# mcu.net
KiCad netlist of a schematic drawn in Altium Designer
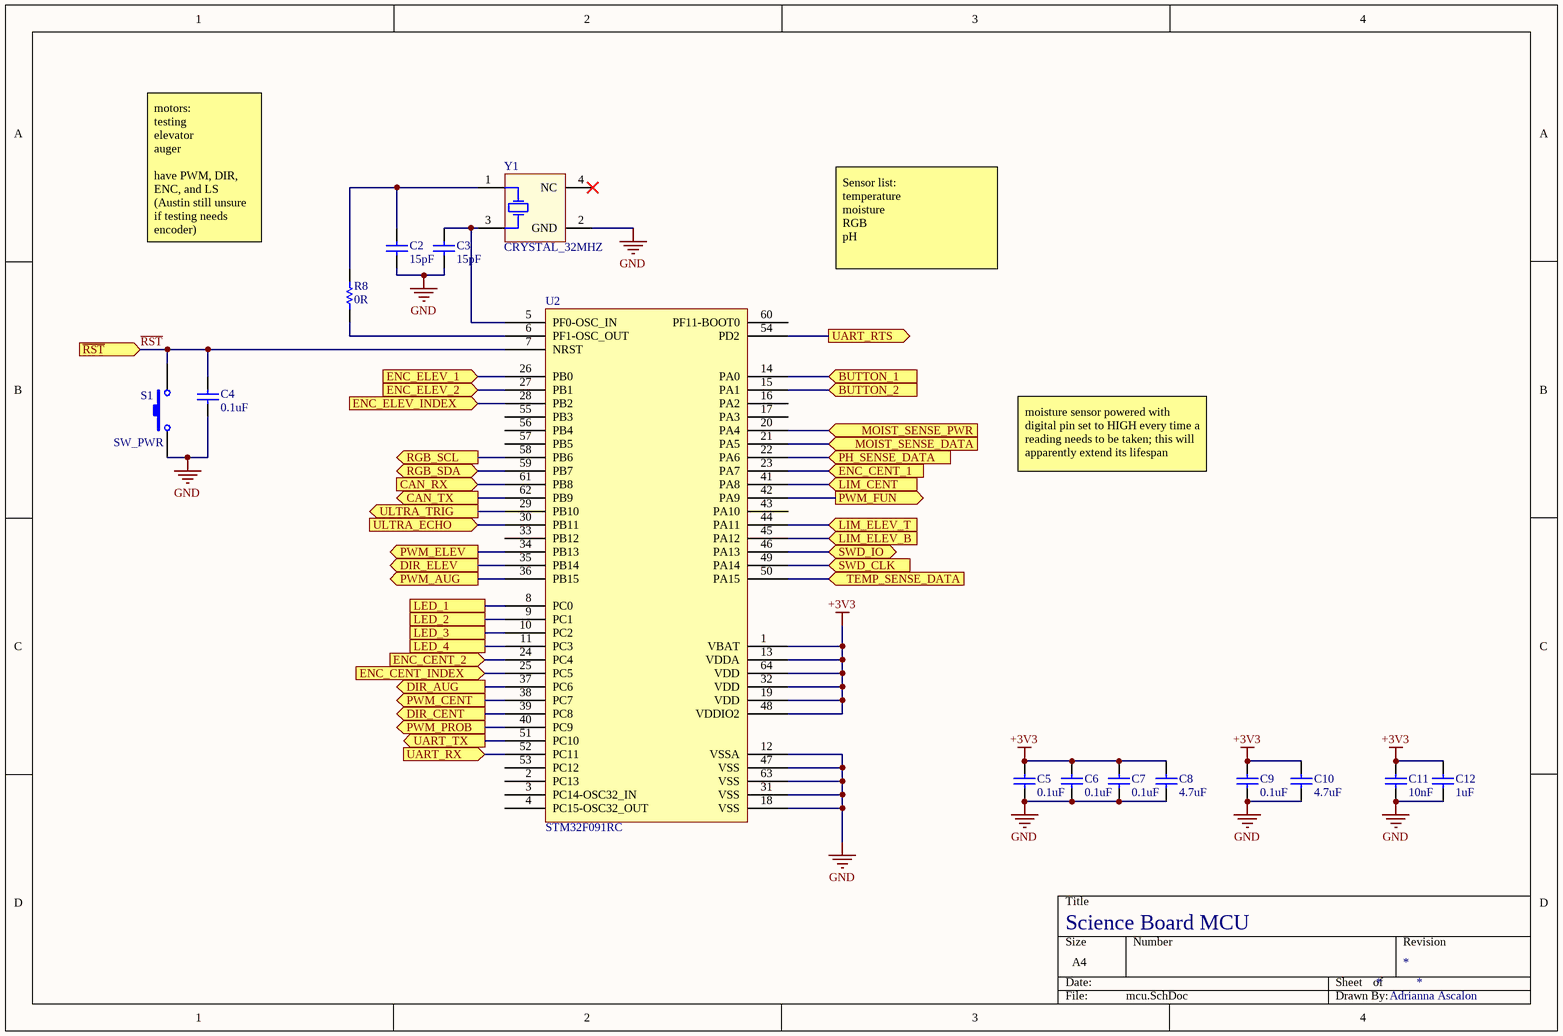
[diagram p0: mcu.SchDoc]

(export (version "E")
  (design (tool "Eeschema 10.0.6"))
  (components
    (comp (ref "C2")
      (value "15pF")
      (footprint "CAPC0603(1608)55_N")
      (description "CAP CER 15PF 250V NPO 0603")
      (fields (field (name "MANUFACTURER") "Yageo") (field (name "MPN") "AC0603JRNPOYBN150"))
      (libsource (lib "UWRT_Schematic_Library_2019") (part "CAP_15pF_0603"))
    )
    (comp (ref "C3")
      (value "15pF")
      (footprint "CAPC0603(1608)55_N")
      (description "CAP CER 15PF 250V NPO 0603")
      (fields (field (name "MANUFACTURER") "Yageo") (field (name "MPN") "AC0603JRNPOYBN150"))
      (libsource (lib "UWRT_Schematic_Library_2019") (part "CAP_15pF_0603"))
    )
    (comp (ref "C4")
      (value "0.1uF")
      (footprint "CAPC0603(1608)55_N")
      (description "CAP CER 0.1UF 16V X7R 0603")
      (fields (field (name "MANUFACTURER") "Yageo") (field (name "MPN") "CC0603KRX7R7BB104"))
      (libsource (lib "UWRT_Schematic_Library_2019") (part "CAP_0.1uF_16V_0603"))
    )
    (comp (ref "C5")
      (value "0.1uF")
      (footprint "CAPC0603(1608)55_N")
      (description "CAP CER 0.1UF 16V X7R 0603")
      (fields (field (name "MANUFACTURER") "Yageo") (field (name "MPN") "CC0603KRX7R7BB104"))
      (libsource (lib "UWRT_Schematic_Library_2019") (part "CAP_0.1uF_16V_0603"))
    )
    (comp (ref "C6")
      (value "0.1uF")
      (footprint "CAPC0603(1608)55_N")
      (description "CAP CER 0.1UF 16V X7R 0603")
      (fields (field (name "MANUFACTURER") "Yageo") (field (name "MPN") "CC0603KRX7R7BB104"))
      (libsource (lib "UWRT_Schematic_Library_2019") (part "CAP_0.1uF_16V_0603"))
    )
    (comp (ref "C7")
      (value "0.1uF")
      (footprint "CAPC0603(1608)55_N")
      (description "CAP CER 0.1UF 16V X7R 0603")
      (fields (field (name "MANUFACTURER") "Yageo") (field (name "MPN") "CC0603KRX7R7BB104"))
      (libsource (lib "UWRT_Schematic_Library_2019") (part "CAP_0.1uF_16V_0603"))
    )
    (comp (ref "C8")
      (value "4.7uF")
      (footprint "CAPC0603(1608)55_N")
      (description "CAP CER 4.7UF 6.3V X5R 0603")
      (fields (field (name "MANUFACTURER") "Yageo") (field (name "MPN") "CC0603KRX5R5BB475"))
      (libsource (lib "UWRT_Schematic_Library_2019") (part "CAP_4.7uF_0603"))
    )
    (comp (ref "C9")
      (value "0.1uF")
      (footprint "CAPC0603(1608)55_N")
      (description "CAP CER 0.1UF 16V X7R 0603")
      (fields (field (name "MANUFACTURER") "Yageo") (field (name "MPN") "CC0603KRX7R7BB104"))
      (libsource (lib "UWRT_Schematic_Library_2019") (part "CAP_0.1uF_16V_0603"))
    )
    (comp (ref "C10")
      (value "4.7uF")
      (footprint "CAPC0603(1608)55_N")
      (description "CAP CER 4.7UF 6.3V X5R 0603")
      (fields (field (name "MANUFACTURER") "Yageo") (field (name "MPN") "CC0603KRX5R5BB475"))
      (libsource (lib "UWRT_Schematic_Library_2019") (part "CAP_4.7uF_0603"))
    )
    (comp (ref "C11")
      (value "10nF")
      (footprint "CAPC0603(1608)55_N")
      (description "CAP CER 10000PF 16V X7R 0603")
      (fields (field (name "MANUFACTURER") "Yageo") (field (name "MPN") "CC0603KRX7R7BB103"))
      (libsource (lib "UWRT_Schematic_Library_2019") (part "CAP_10nF_0603"))
    )
    (comp (ref "C12")
      (value "1uF")
      (footprint "CAPC0603(1608)55_N")
      (description "CAP CER 1UF 16V Y5V 0603")
      (fields (field (name "MANUFACTURER") "Yageo") (field (name "MPN") "CC0603ZRY5V7BB105"))
      (libsource (lib "UWRT_Schematic_Library_2019") (part "CAP_1uF_16V_0603"))
    )
    (comp (ref "R8")
      (value "0R")
      (footprint "RESC0603(1608)_N")
      (description "RES SMD 0 OHM JUMPER 1/10W 0603")
      (fields (field (name "MANUFACTURER") "Yageo") (field (name "MPN") "RC0603JR-070RL"))
      (libsource (lib "UWRT_Schematic_Library_2019") (part "RES_0R_0603"))
    )
    (comp (ref "S1")
      (value "SW_PWR")
      (footprint "PTS830GM140")
      (description "Power Switch (Red)")
      (fields
        (field (name "MPN") "PTS830GM140 SMTR LFS")
        (field (name "DIGIKEY PART NUMBER") "CKN10587CT-ND")
      )
      (libsource (lib "UWRT_Schematic_Library_2019") (part "SW_PWR"))
    )
    (comp (ref "U2")
      (value "STM32F091RC")
      (footprint "UWRT_Footprint_Library_2019:STM_LQFP64_N")
      (fields
        (field (name "MANUFACTURER") "STMicroelectronics")
        (field (name "DIGIKEY PART NUMBER") "497-15167-ND")
      )
      (libsource (lib "UWRT_Schematic_Library_2019") (part "STM32F091RC"))
    )
    (comp (ref "Y1")
      (value "CRYSTAL_32MHZ")
      (footprint "AVX-CX2520DB32000D0GEJZ1-4_V")
      (description "CRYSTAL 32MHZ 8PF SMD")
      (fields
        (field (name "MANUFACTURER") "Kyocera International Inc. Electronic Components")
        (field (name "MPN") "CX2520DB32000D0GPSC1")
      )
      (libsource (lib "UWRT_Schematic_Library_2019") (part "CRYSTAL_32MHZ"))
    )
  )
  (nets
    (net (code "1") (name "+3V3") (class "Default")
      (node (ref "C10") (pin "2") (pinfunction "2_2") (pintype "passive"))
      (node (ref "C11") (pin "2") (pinfunction "2_2") (pintype "passive"))
      (node (ref "C12") (pin "2") (pinfunction "2_2") (pintype "passive"))
      (node (ref "C5") (pin "1") (pinfunction "1_1") (pintype "passive"))
      (node (ref "C6") (pin "1") (pinfunction "1_1") (pintype "passive"))
      (node (ref "C7") (pin "1") (pinfunction "1_1") (pintype "passive"))
      (node (ref "C8") (pin "2") (pinfunction "2_2") (pintype "passive"))
      (node (ref "C9") (pin "1") (pinfunction "1_1") (pintype "passive"))
      (node (ref "U2") (pin "1") (pinfunction "VBAT_1") (pintype "passive"))
      (node (ref "U2") (pin "13") (pinfunction "VDDA_13") (pintype "passive"))
      (node (ref "U2") (pin "19") (pinfunction "VDD_19") (pintype "passive"))
      (node (ref "U2") (pin "32") (pinfunction "VDD_32") (pintype "passive"))
      (node (ref "U2") (pin "48") (pinfunction "VDDIO2_48") (pintype "passive"))
      (node (ref "U2") (pin "64") (pinfunction "VDD_64") (pintype "passive"))
    )
    (net (code "2") (name "/BUTTON_1") (class "Default")
      (node (ref "U2") (pin "14") (pinfunction "PA0_14") (pintype "passive"))
    )
    (net (code "3") (name "/BUTTON_2") (class "Default")
      (node (ref "U2") (pin "15") (pinfunction "PA1_15") (pintype "passive"))
    )
    (net (code "4") (name "/CAN_RX") (class "Default")
      (node (ref "U2") (pin "61") (pinfunction "PB8_61") (pintype "passive"))
    )
    (net (code "5") (name "/CAN_TX") (class "Default")
      (node (ref "U2") (pin "62") (pinfunction "PB9_62") (pintype "passive"))
    )
    (net (code "6") (name "/DIR_AUG") (class "Default")
      (node (ref "U2") (pin "37") (pinfunction "PC6_37") (pintype "passive"))
    )
    (net (code "7") (name "/DIR_CENT") (class "Default")
      (node (ref "U2") (pin "39") (pinfunction "PC8_39") (pintype "passive"))
    )
    (net (code "8") (name "/DIR_ELEV") (class "Default")
      (node (ref "U2") (pin "35") (pinfunction "PB14_35") (pintype "passive"))
    )
    (net (code "9") (name "/ENC_CENT_1") (class "Default")
      (node (ref "U2") (pin "23") (pinfunction "PA7_23") (pintype "passive"))
    )
    (net (code "10") (name "/ENC_CENT_2") (class "Default")
      (node (ref "U2") (pin "24") (pinfunction "PC4_24") (pintype "passive"))
    )
    (net (code "11") (name "/ENC_CENT_INDEX") (class "Default")
      (node (ref "U2") (pin "25") (pinfunction "PC5_25") (pintype "passive"))
    )
    (net (code "12") (name "/ENC_ELEV_1") (class "Default")
      (node (ref "U2") (pin "26") (pinfunction "PB0_26") (pintype "passive"))
    )
    (net (code "13") (name "/ENC_ELEV_2") (class "Default")
      (node (ref "U2") (pin "27") (pinfunction "PB1_27") (pintype "passive"))
    )
    (net (code "14") (name "/ENC_ELEV_INDEX") (class "Default")
      (node (ref "U2") (pin "28") (pinfunction "PB2_28") (pintype "passive"))
    )
    (net (code "15") (name "/LED_1") (class "Default")
      (node (ref "U2") (pin "8") (pinfunction "PC0_8") (pintype "passive"))
    )
    (net (code "16") (name "/LED_2") (class "Default")
      (node (ref "U2") (pin "9") (pinfunction "PC1_9") (pintype "passive"))
    )
    (net (code "17") (name "/LED_3") (class "Default")
      (node (ref "U2") (pin "10") (pinfunction "PC2_10") (pintype "passive"))
    )
    (net (code "18") (name "/LED_4") (class "Default")
      (node (ref "U2") (pin "11") (pinfunction "PC3_11") (pintype "passive"))
    )
    (net (code "19") (name "/LIM_CENT") (class "Default")
      (node (ref "U2") (pin "41") (pinfunction "PA8_41") (pintype "passive"))
    )
    (net (code "20") (name "/LIM_ELEV_B") (class "Default")
      (node (ref "U2") (pin "45") (pinfunction "PA12_45") (pintype "passive"))
    )
    (net (code "21") (name "/LIM_ELEV_T") (class "Default")
      (node (ref "U2") (pin "44") (pinfunction "PA11_44") (pintype "passive"))
    )
    (net (code "22") (name "/MOIST_SENSE_DATA") (class "Default")
      (node (ref "U2") (pin "21") (pinfunction "PA5_21") (pintype "passive"))
    )
    (net (code "23") (name "/MOIST_SENSE_PWR") (class "Default")
      (node (ref "U2") (pin "20") (pinfunction "PA4_20") (pintype "passive"))
    )
    (net (code "24") (name "/PH_SENSE_DATA") (class "Default")
      (node (ref "U2") (pin "22") (pinfunction "PA6_22") (pintype "passive"))
    )
    (net (code "25") (name "/PWM_AUG") (class "Default")
      (node (ref "U2") (pin "36") (pinfunction "PB15_36") (pintype "passive"))
    )
    (net (code "26") (name "/PWM_CENT") (class "Default")
      (node (ref "U2") (pin "38") (pinfunction "PC7_38") (pintype "passive"))
    )
    (net (code "27") (name "/PWM_ELEV") (class "Default")
      (node (ref "U2") (pin "34") (pinfunction "PB13_34") (pintype "passive"))
    )
    (net (code "28") (name "/PWM_FUN") (class "Default")
      (node (ref "U2") (pin "42") (pinfunction "PA9_42") (pintype "passive"))
    )
    (net (code "29") (name "/PWM_PROB") (class "Default")
      (node (ref "U2") (pin "40") (pinfunction "PC9_40") (pintype "passive"))
    )
    (net (code "30") (name "/RGB_SCL") (class "Default")
      (node (ref "U2") (pin "58") (pinfunction "PB6_58") (pintype "passive"))
    )
    (net (code "31") (name "/RGB_SDA") (class "Default")
      (node (ref "U2") (pin "59") (pinfunction "PB7_59") (pintype "passive"))
    )
    (net (code "32") (name "/SWD_CLK") (class "Default")
      (node (ref "U2") (pin "49") (pinfunction "PA14_49") (pintype "passive"))
    )
    (net (code "33") (name "/SWD_IO") (class "Default")
      (node (ref "U2") (pin "46") (pinfunction "PA13_46") (pintype "passive"))
    )
    (net (code "34") (name "/TEMP_SENSE_DATA") (class "Default")
      (node (ref "U2") (pin "50") (pinfunction "PA15_50") (pintype "passive"))
    )
    (net (code "35") (name "/UART_RTS") (class "Default")
      (node (ref "U2") (pin "54") (pinfunction "PD2_54") (pintype "passive"))
    )
    (net (code "36") (name "/UART_RX") (class "Default")
      (node (ref "U2") (pin "52") (pinfunction "PC11_52") (pintype "passive"))
    )
    (net (code "37") (name "/UART_TX") (class "Default")
      (node (ref "U2") (pin "51") (pinfunction "PC10_51") (pintype "passive"))
    )
    (net (code "38") (name "/ULTRA_ECHO") (class "Default")
      (node (ref "U2") (pin "30") (pinfunction "PB11_30") (pintype "passive"))
    )
    (net (code "39") (name "/ULTRA_TRIG") (class "Default")
      (node (ref "U2") (pin "29") (pinfunction "PB10_29") (pintype "passive"))
    )
    (net (code "40") (name "/~{RST}") (class "Default")
      (node (ref "C4") (pin "2") (pinfunction "2_2") (pintype "passive"))
      (node (ref "S1") (pin "2") (pinfunction "2_2") (pintype "passive"))
      (node (ref "U2") (pin "7") (pinfunction "NRST_7") (pintype "passive"))
    )
    (net (code "41") (name "GND") (class "Default")
      (node (ref "C10") (pin "1") (pinfunction "1_1") (pintype "passive"))
      (node (ref "C11") (pin "1") (pinfunction "1_1") (pintype "passive"))
      (node (ref "C12") (pin "1") (pinfunction "1_1") (pintype "passive"))
      (node (ref "C2") (pin "1") (pinfunction "1_1") (pintype "passive"))
      (node (ref "C3") (pin "1") (pinfunction "1_1") (pintype "passive"))
      (node (ref "C4") (pin "1") (pinfunction "1_1") (pintype "passive"))
      (node (ref "C5") (pin "2") (pinfunction "2_2") (pintype "passive"))
      (node (ref "C6") (pin "2") (pinfunction "2_2") (pintype "passive"))
      (node (ref "C7") (pin "2") (pinfunction "2_2") (pintype "passive"))
      (node (ref "C8") (pin "1") (pinfunction "1_1") (pintype "passive"))
      (node (ref "C9") (pin "2") (pinfunction "2_2") (pintype "passive"))
      (node (ref "S1") (pin "1") (pinfunction "1_1") (pintype "passive"))
      (node (ref "U2") (pin "12") (pinfunction "VSSA_12") (pintype "passive"))
      (node (ref "U2") (pin "18") (pinfunction "VSS_18") (pintype "passive"))
      (node (ref "U2") (pin "31") (pinfunction "VSS_31") (pintype "passive"))
      (node (ref "U2") (pin "47") (pinfunction "VSS_47") (pintype "passive"))
      (node (ref "U2") (pin "63") (pinfunction "VSS_63") (pintype "passive"))
      (node (ref "Y1") (pin "2") (pinfunction "GND_2") (pintype "power_in"))
    )
    (net (code "42") (name "Net-(C2-Pad2)") (class "Default")
      (node (ref "C2") (pin "2") (pinfunction "2_2") (pintype "passive"))
      (node (ref "R8") (pin "2") (pinfunction "2_2") (pintype "passive"))
      (node (ref "Y1") (pin "1") (pinfunction "HOT_1") (pintype "passive"))
    )
    (net (code "43") (name "Net-(U2-PF0-OSC_IN)") (class "Default")
      (node (ref "C3") (pin "2") (pinfunction "2_2") (pintype "passive"))
      (node (ref "U2") (pin "5") (pinfunction "PF0-OSC_IN_5") (pintype "passive"))
      (node (ref "Y1") (pin "3") (pinfunction "HOT_3") (pintype "passive"))
    )
    (net (code "44") (name "Net-(U2-PF1-OSC_OUT)") (class "Default")
      (node (ref "R8") (pin "1") (pinfunction "1_1") (pintype "passive"))
      (node (ref "U2") (pin "6") (pinfunction "PF1-OSC_OUT_6") (pintype "passive"))
    )
    (net (code "45") (name "unconnected-(U2-PA2-Pad16)") (class "Default")
      (node (ref "U2") (pin "16") (pinfunction "PA2_16") (pintype "passive"))
    )
    (net (code "46") (name "unconnected-(U2-PA3-Pad17)") (class "Default")
      (node (ref "U2") (pin "17") (pinfunction "PA3_17") (pintype "passive"))
    )
    (net (code "47") (name "unconnected-(U2-PA10-Pad43)") (class "Default")
      (node (ref "U2") (pin "43") (pinfunction "PA10_43") (pintype "passive"))
    )
    (net (code "48") (name "unconnected-(U2-PB3-Pad55)") (class "Default")
      (node (ref "U2") (pin "55") (pinfunction "PB3_55") (pintype "passive"))
    )
    (net (code "49") (name "unconnected-(U2-PB4-Pad56)") (class "Default")
      (node (ref "U2") (pin "56") (pinfunction "PB4_56") (pintype "passive"))
    )
    (net (code "50") (name "unconnected-(U2-PB5-Pad57)") (class "Default")
      (node (ref "U2") (pin "57") (pinfunction "PB5_57") (pintype "passive"))
    )
    (net (code "51") (name "unconnected-(U2-PB12-Pad33)") (class "Default")
      (node (ref "U2") (pin "33") (pinfunction "PB12_33") (pintype "passive"))
    )
    (net (code "52") (name "unconnected-(U2-PC12-Pad53)") (class "Default")
      (node (ref "U2") (pin "53") (pinfunction "PC12_53") (pintype "passive"))
    )
    (net (code "53") (name "unconnected-(U2-PC13-Pad2)") (class "Default")
      (node (ref "U2") (pin "2") (pinfunction "PC13_2") (pintype "passive"))
    )
    (net (code "54") (name "unconnected-(U2-PC14-OSC32_IN-Pad3)") (class "Default")
      (node (ref "U2") (pin "3") (pinfunction "PC14-OSC32_IN_3") (pintype "passive"))
    )
    (net (code "55") (name "unconnected-(U2-PC15-OSC32_OUT-Pad4)") (class "Default")
      (node (ref "U2") (pin "4") (pinfunction "PC15-OSC32_OUT_4") (pintype "passive"))
    )
    (net (code "56") (name "unconnected-(U2-PF11-BOOT0-Pad60)") (class "Default")
      (node (ref "U2") (pin "60") (pinfunction "PF11-BOOT0_60") (pintype "passive"))
    )
    (net (code "57") (name "unconnected-(Y1-NC-Pad4)") (class "Default")
      (node (ref "Y1") (pin "4") (pinfunction "NC_4") (pintype "passive+no_connect"))
    )
  )
)
